# ProPrj_picoballoon-tracker_2025-08-19.net
KiCad netlist of a schematic drawn in EasyEDA Pro
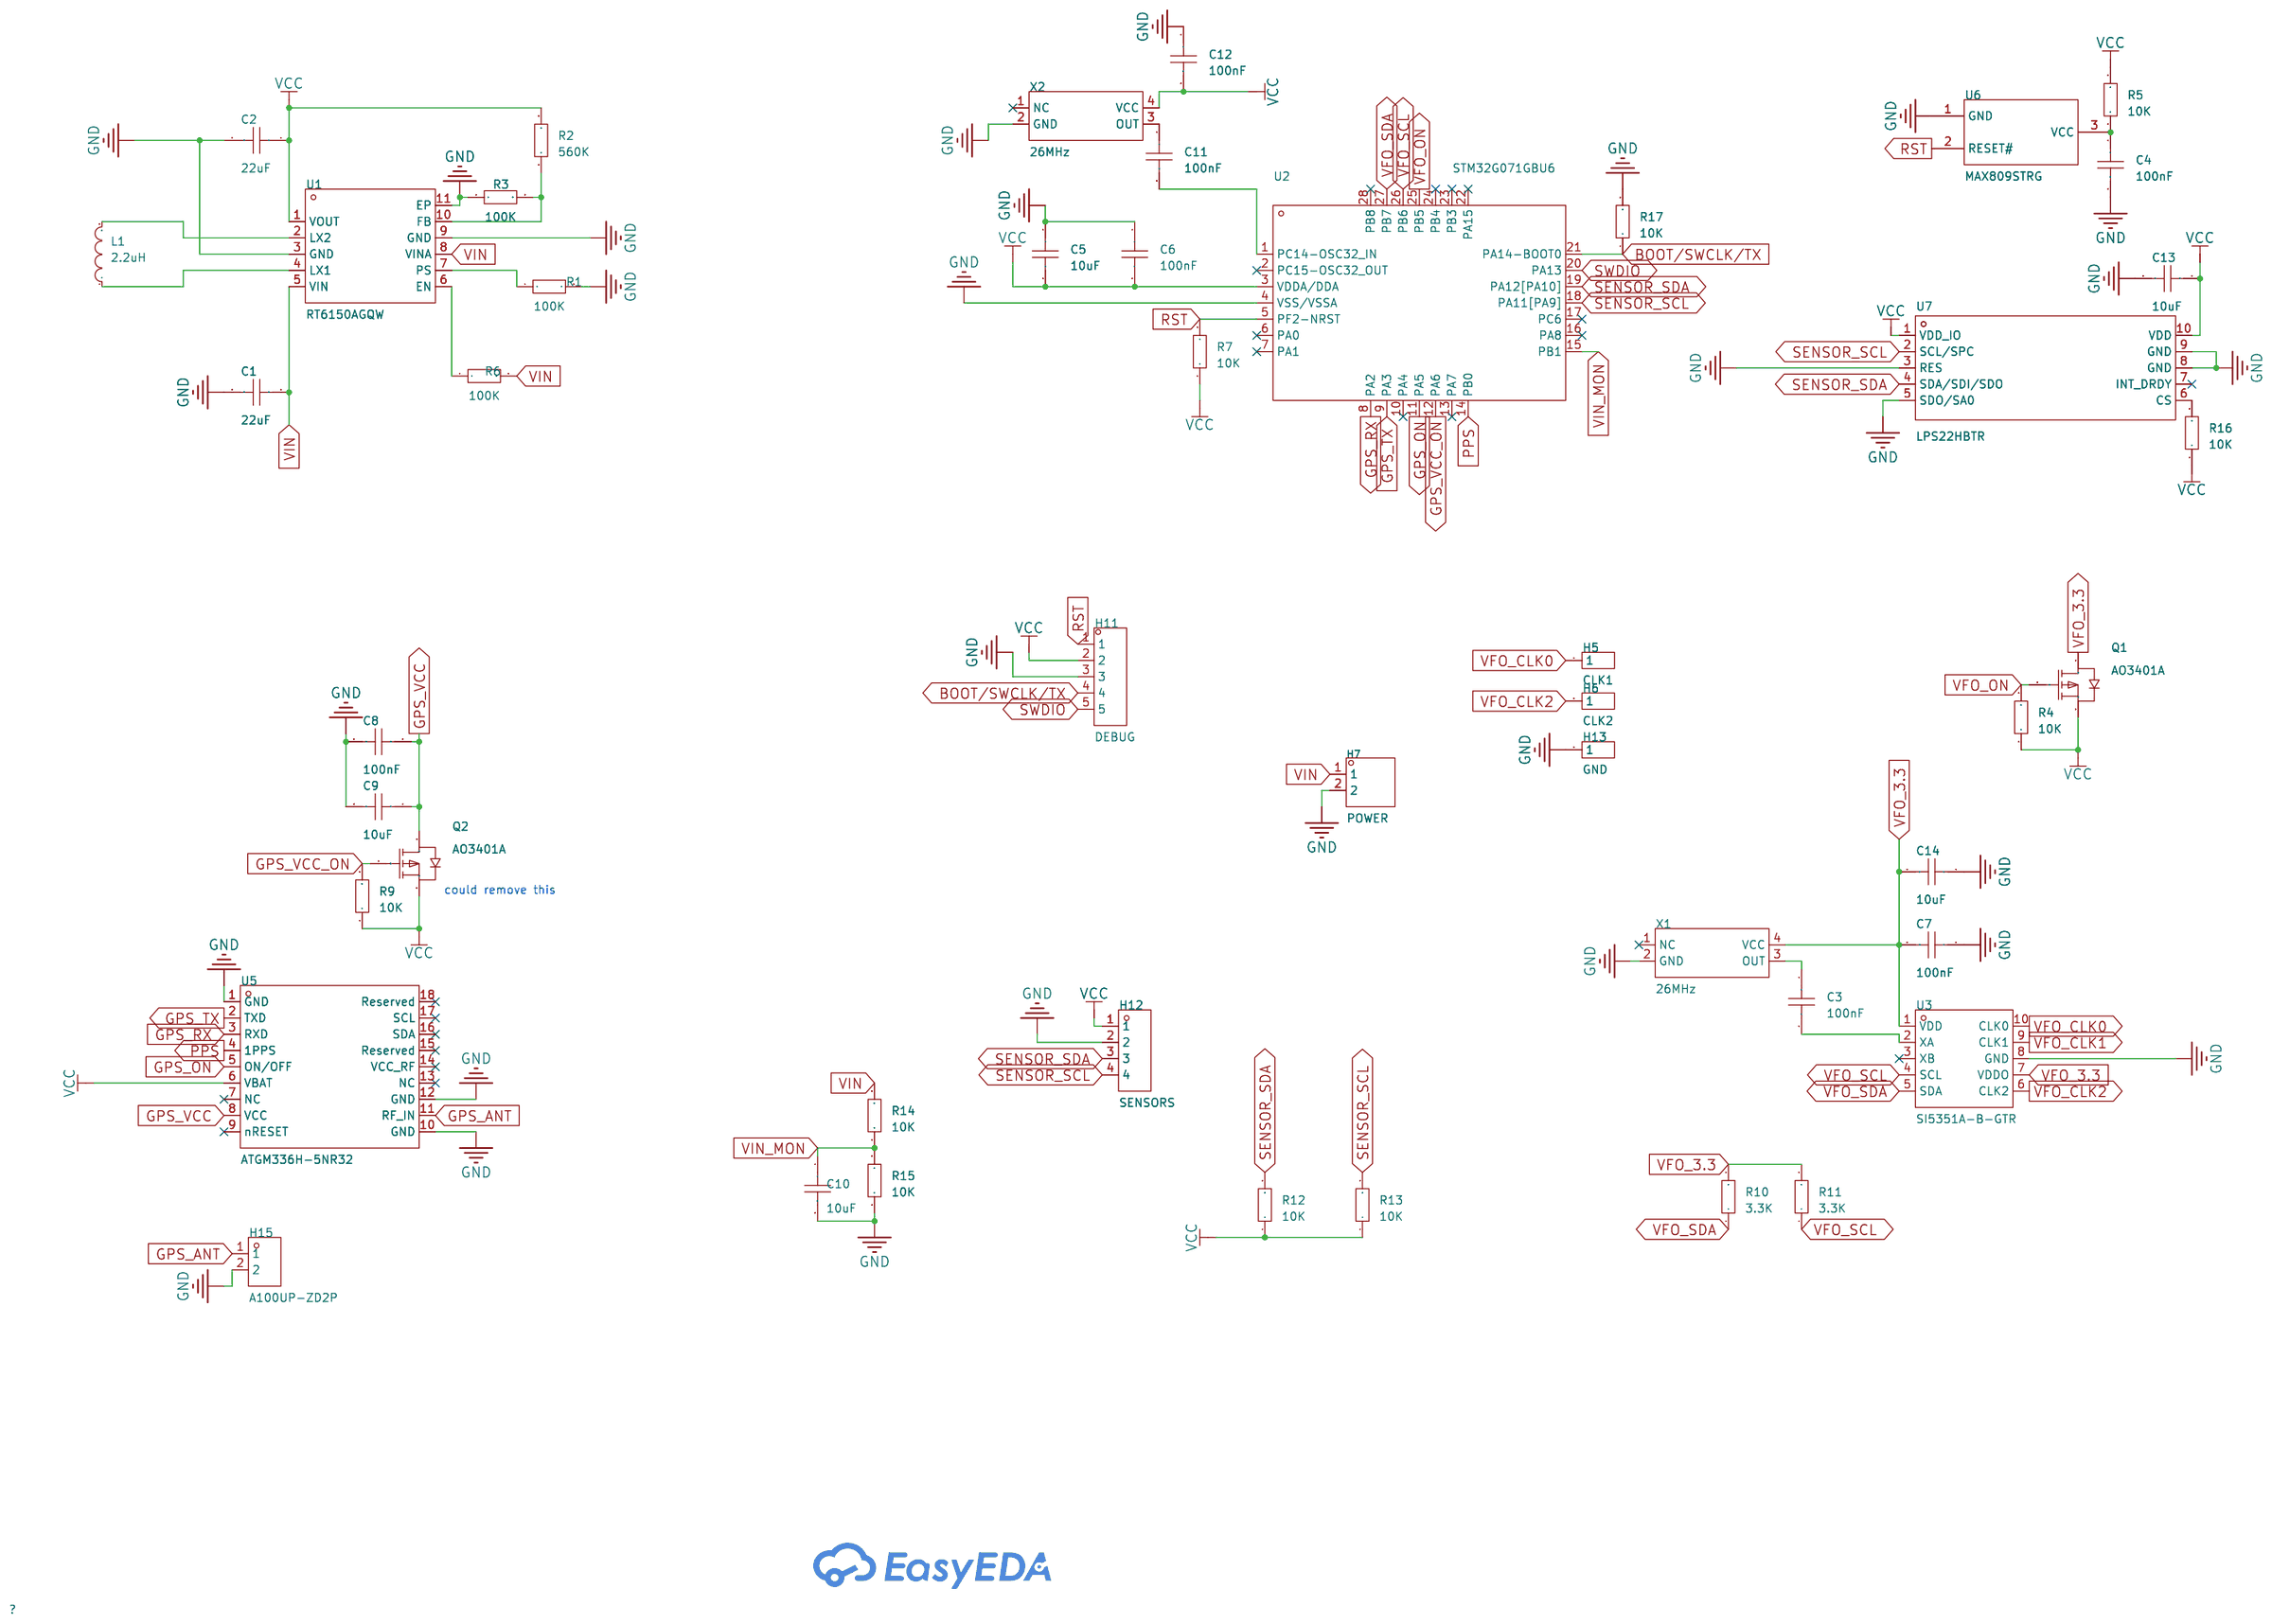
[diagram p0: schematic sheet]

(export (version "E")
  (design (tool "Eeschema 10.0.6"))
  (components
    (comp (ref "C1")
      (value "22uF")
      (footprint "easyedapro:C0402")
      (libsource (lib "easyedapro") (part "CAP"))
    )
    (comp (ref "C2")
      (value "22uF")
      (footprint "easyedapro:C0402")
      (libsource (lib "easyedapro") (part "CAP"))
    )
    (comp (ref "C3")
      (value "100nF")
      (footprint "easyedapro:C0402")
      (libsource (lib "easyedapro") (part "CAP"))
    )
    (comp (ref "C4")
      (value "100nF")
      (footprint "easyedapro:C0402")
      (libsource (lib "easyedapro") (part "CAP"))
    )
    (comp (ref "C5")
      (value "10uF")
      (footprint "easyedapro:C0402")
      (libsource (lib "easyedapro") (part "CAP"))
    )
    (comp (ref "C6")
      (value "100nF")
      (footprint "easyedapro:C0402")
      (libsource (lib "easyedapro") (part "CAP"))
    )
    (comp (ref "C7")
      (value "100nF")
      (footprint "easyedapro:C0402")
      (libsource (lib "easyedapro") (part "CAP"))
    )
    (comp (ref "C8")
      (value "100nF")
      (footprint "easyedapro:C0402")
      (libsource (lib "easyedapro") (part "CAP"))
    )
    (comp (ref "C9")
      (value "10uF")
      (footprint "easyedapro:C0402")
      (libsource (lib "easyedapro") (part "CAP"))
    )
    (comp (ref "C10")
      (value "10uF")
      (footprint "easyedapro:C0402")
      (libsource (lib "easyedapro") (part "CAP"))
    )
    (comp (ref "C11")
      (value "100nF")
      (footprint "easyedapro:C0402")
      (libsource (lib "easyedapro") (part "CAP"))
    )
    (comp (ref "C12")
      (value "100nF")
      (footprint "easyedapro:C0402")
      (libsource (lib "easyedapro") (part "CAP"))
    )
    (comp (ref "C13")
      (value "10uF")
      (footprint "easyedapro:C0402")
      (libsource (lib "easyedapro") (part "CAP"))
    )
    (comp (ref "C14")
      (value "10uF")
      (footprint "easyedapro:C0402")
      (libsource (lib "easyedapro") (part "CAP"))
    )
    (comp (ref "H5")
      (value "CLK1")
      (footprint "easyedapro:HDR-TH_1P-V-M_XKB_X4611WV-01I-C28D40")
      (libsource (lib "easyedapro") (part "HDR_1x1"))
    )
    (comp (ref "H6")
      (value "CLK2")
      (footprint "easyedapro:HDR-TH_1P-V-M_XKB_X4611WV-01I-C28D40")
      (libsource (lib "easyedapro") (part "HDR_1x1"))
    )
    (comp (ref "H7")
      (value "POWER")
      (footprint "easyedapro:HDR-TH_2P-P2.54-V-M-1")
      (libsource (lib "easyedapro") (part "210S-1*2P L=11.6MMGold-plated black"))
    )
    (comp (ref "H11")
      (value "DEBUG")
      (footprint "easyedapro:HDR-TH_5P-P2.54-V-M")
      (libsource (lib "easyedapro") (part "MTP125-1105S1"))
    )
    (comp (ref "H12")
      (value "SENSORS")
      (footprint "easyedapro:HDR-TH_ZX-PZ1.0-1-4PZZ")
      (fields
        (field (name "Manufacturer Part") "ZX-PZ1.0-1-4PZZ")
        (field (name "Manufacturer") "Megastar(兆星)")
      )
      (libsource (lib "easyedapro") (part "ZX-PZ1.0-1-4PZZ"))
    )
    (comp (ref "H13")
      (value "GND")
      (footprint "easyedapro:HDR-TH_1P-V-M_XKB_X4611WV-01I-C28D40")
      (libsource (lib "easyedapro") (part "HDR_1x1"))
    )
    (comp (ref "H15")
      (value "A100UP-ZD2P")
      (footprint "easyedapro:HDR-TH_2P-P1.00-V-M")
      (fields (field (name "Manufacturer") "BXCONN(宝讯)"))
      (libsource (lib "easyedapro") (part "A100UP-ZD2P"))
    )
    (comp (ref "L1")
      (value "2.2uH")
      (footprint "easyedapro:L0805")
      (libsource (lib "easyedapro") (part "电感"))
    )
    (comp (ref "Q1")
      (value "AO3401A")
      (footprint "easyedapro:SOT-23_L2.9-W1.3-P1.90-LS2.4-BR")
      (fields (field (name "Manufacturer") "AOS"))
      (libsource (lib "easyedapro") (part "AO3401A"))
    )
    (comp (ref "Q2")
      (value "AO3401A")
      (footprint "easyedapro:SOT-23_L2.9-W1.3-P1.90-LS2.4-BR")
      (fields (field (name "Manufacturer") "AOS"))
      (libsource (lib "easyedapro") (part "AO3401A"))
    )
    (comp (ref "R1")
      (value "100K")
      (footprint "easyedapro:R0402")
      (libsource (lib "easyedapro") (part "Res"))
    )
    (comp (ref "R2")
      (value "560K")
      (footprint "easyedapro:R0402")
      (libsource (lib "easyedapro") (part "Res"))
    )
    (comp (ref "R3")
      (value "100K")
      (footprint "easyedapro:R0402")
      (libsource (lib "easyedapro") (part "Res"))
    )
    (comp (ref "R4") (value "10K") (footprint "easyedapro:R0402") (libsource (lib "easyedapro") (part "Res")))
    (comp (ref "R5") (value "10K") (footprint "easyedapro:R0402") (libsource (lib "easyedapro") (part "Res")))
    (comp (ref "R6")
      (value "100K")
      (footprint "easyedapro:R0402")
      (libsource (lib "easyedapro") (part "Res"))
    )
    (comp (ref "R7") (value "10K") (footprint "easyedapro:R0402") (libsource (lib "easyedapro") (part "Res")))
    (comp (ref "R9") (value "10K") (footprint "easyedapro:R0402") (libsource (lib "easyedapro") (part "Res")))
    (comp (ref "R10")
      (value "3.3K")
      (footprint "easyedapro:R0402")
      (libsource (lib "easyedapro") (part "Res"))
    )
    (comp (ref "R11")
      (value "3.3K")
      (footprint "easyedapro:R0402")
      (libsource (lib "easyedapro") (part "Res"))
    )
    (comp (ref "R12")
      (value "10K")
      (footprint "easyedapro:R0402")
      (libsource (lib "easyedapro") (part "Res"))
    )
    (comp (ref "R13")
      (value "10K")
      (footprint "easyedapro:R0402")
      (libsource (lib "easyedapro") (part "Res"))
    )
    (comp (ref "R14")
      (value "10K")
      (footprint "easyedapro:R0402")
      (libsource (lib "easyedapro") (part "Res"))
    )
    (comp (ref "R15")
      (value "10K")
      (footprint "easyedapro:R0402")
      (libsource (lib "easyedapro") (part "Res"))
    )
    (comp (ref "R16")
      (value "10K")
      (footprint "easyedapro:R0402")
      (libsource (lib "easyedapro") (part "Res"))
    )
    (comp (ref "R17")
      (value "10K")
      (footprint "easyedapro:R0402")
      (libsource (lib "easyedapro") (part "Res"))
    )
    (comp (ref "U1")
      (value "RT6150AGQW")
      (footprint "easyedapro:WDFN-10_L3.0-W3.0-P0.50-BL-EP")
      (fields (field (name "Manufacturer") "RICHTEK(立锜)"))
      (libsource (lib "easyedapro") (part "RT6150AGQW"))
    )
    (comp (ref "U2")
      (value "STM32G071GBU6")
      (footprint "easyedapro:UFQFPN-28_L4.0-W4.0-P0.50-BL")
      (fields (field (name "Manufacturer") "ST(意法半导体)"))
      (libsource (lib "easyedapro") (part "STM32G071GBU6"))
    )
    (comp (ref "U3")
      (value "SI5351A-B-GTR")
      (footprint "easyedapro:MSOP-10_L3.0-W3.0-P0.50-LS5.0-BL")
      (fields (field (name "Manufacturer") "SKYWORKS/SILICON LABS(芯科)"))
      (libsource (lib "easyedapro") (part "SI5351A-B-GTR"))
    )
    (comp (ref "U5")
      (value "ATGM336H-5NR32")
      (footprint "easyedapro:GPS-SMD_18P-L10.1-W9.7-P1.10-TL")
      (fields (field (name "Manufacturer") "杭州中科微"))
      (libsource (lib "easyedapro") (part "ATGM336H-5NR-32"))
    )
    (comp (ref "U6")
      (value "MAX809STRG")
      (footprint "easyedapro:SOT-23-3_L2.9-W1.6-P1.90-LS2.8-BR")
      (fields (field (name "Manufacturer") "onsemi(安森美)"))
      (libsource (lib "easyedapro") (part "MAX809STRG"))
    )
    (comp (ref "U7")
      (value "LPS22HBTR")
      (footprint "easyedapro:HLGA-10L_LPS22HBTR")
      (fields (field (name "Manufacturer") "ST(意法半导体)"))
      (libsource (lib "easyedapro") (part "LPS22HBTR"))
    )
    (comp (ref "X1")
      (value "26MHz")
      (footprint "easyedapro:OSC-SMD_4P-L2.5-W2.0-BL_X1G0042110003")
      (fields (field (name "Manufacturer Part") "X1G0042110003") (field (name "Manufacturer") "EPSON(爱普生)"))
      (libsource (lib "easyedapro") (part "X1G0042110003_C3013793"))
    )
    (comp (ref "X2")
      (value "26MHz")
      (footprint "easyedapro:OSC-SMD_4P-L2.5-W2.0-BL_X1G0042110003")
      (fields (field (name "Manufacturer Part") "X1G0042110003") (field (name "Manufacturer") "EPSON(爱普生)"))
      (libsource (lib "easyedapro") (part "X1G0042110003_C3013793"))
    )
  )
  (nets
    (net (code "1") (name "BOOT{slash}SWCLK{slash}TX") (class "Default")
      (node (ref "H11") (pin "4") (pinfunction "4_4") (pintype "input"))
      (node (ref "R17") (pin "1") (pinfunction "1_1") (pintype "input"))
      (node (ref "U2") (pin "21") (pinfunction "PA14-BOOT0_21") (pintype "unspecified"))
    )
    (net (code "2") (name "GND") (class "Default")
      (node (ref "C1") (pin "2") (pinfunction "2_2") (pintype "input"))
      (node (ref "C10") (pin "2") (pinfunction "2_2") (pintype "input"))
      (node (ref "C12") (pin "1") (pinfunction "1_1") (pintype "input"))
      (node (ref "C13") (pin "2") (pinfunction "2_2") (pintype "input"))
      (node (ref "C14") (pin "1") (pinfunction "1_1") (pintype "input"))
      (node (ref "C2") (pin "2") (pinfunction "2_2") (pintype "input"))
      (node (ref "C4") (pin "2") (pinfunction "2_2") (pintype "input"))
      (node (ref "C5") (pin "1") (pinfunction "1_1") (pintype "input"))
      (node (ref "C6") (pin "1") (pinfunction "1_1") (pintype "input"))
      (node (ref "C7") (pin "1") (pinfunction "1_1") (pintype "input"))
      (node (ref "C8") (pin "2") (pinfunction "2_2") (pintype "input"))
      (node (ref "C9") (pin "2") (pinfunction "2_2") (pintype "input"))
      (node (ref "H11") (pin "3") (pinfunction "3_3") (pintype "input"))
      (node (ref "H12") (pin "2") (pinfunction "2_2") (pintype "unspecified"))
      (node (ref "H13") (pin "1") (pinfunction "1_1") (pintype "unspecified"))
      (node (ref "H15") (pin "2") (pinfunction "2_2") (pintype "unspecified"))
      (node (ref "H7") (pin "2") (pinfunction "2_2") (pintype "input"))
      (node (ref "R1") (pin "2") (pinfunction "2_2") (pintype "input"))
      (node (ref "R15") (pin "1") (pinfunction "1_1") (pintype "input"))
      (node (ref "R17") (pin "2") (pinfunction "2_2") (pintype "input"))
      (node (ref "R3") (pin "1") (pinfunction "1_1") (pintype "input"))
      (node (ref "U1") (pin "11") (pinfunction "EP_11") (pintype "unspecified"))
      (node (ref "U1") (pin "3") (pinfunction "GND_3") (pintype "unspecified"))
      (node (ref "U1") (pin "9") (pinfunction "GND_9") (pintype "unspecified"))
      (node (ref "U2") (pin "4") (pinfunction "VSS/VSSA_4") (pintype "unspecified"))
      (node (ref "U3") (pin "8") (pinfunction "GND_8") (pintype "unspecified"))
      (node (ref "U5") (pin "1") (pinfunction "GND_1") (pintype "unspecified"))
      (node (ref "U5") (pin "10") (pinfunction "GND_10") (pintype "unspecified"))
      (node (ref "U5") (pin "12") (pinfunction "GND_12") (pintype "unspecified"))
      (node (ref "U6") (pin "1") (pinfunction "GND_1") (pintype "unspecified"))
      (node (ref "U7") (pin "3") (pinfunction "RES_3") (pintype "unspecified"))
      (node (ref "U7") (pin "5") (pinfunction "SDO/SA0_5") (pintype "unspecified"))
      (node (ref "U7") (pin "8") (pinfunction "GND_8") (pintype "unspecified"))
      (node (ref "U7") (pin "9") (pinfunction "GND_9") (pintype "unspecified"))
      (node (ref "X1") (pin "2") (pinfunction "GND_2") (pintype "unspecified"))
      (node (ref "X2") (pin "2") (pinfunction "GND_2") (pintype "unspecified"))
    )
    (net (code "3") (name "GPS_ANT") (class "Default")
      (node (ref "H15") (pin "1") (pinfunction "1_1") (pintype "unspecified"))
      (node (ref "U5") (pin "11") (pinfunction "RF_IN_11") (pintype "unspecified"))
    )
    (net (code "4") (name "GPS_ON") (class "Default")
      (node (ref "U2") (pin "11") (pinfunction "PA5_11") (pintype "unspecified"))
      (node (ref "U5") (pin "5") (pinfunction "ON/OFF_5") (pintype "unspecified"))
    )
    (net (code "5") (name "GPS_RX") (class "Default")
      (node (ref "U2") (pin "8") (pinfunction "PA2_8") (pintype "unspecified"))
      (node (ref "U5") (pin "3") (pinfunction "RXD_3") (pintype "unspecified"))
    )
    (net (code "6") (name "GPS_TX") (class "Default")
      (node (ref "U2") (pin "9") (pinfunction "PA3_9") (pintype "unspecified"))
      (node (ref "U5") (pin "2") (pinfunction "TXD_2") (pintype "unspecified"))
    )
    (net (code "7") (name "GPS_VCC") (class "Default")
      (node (ref "C8") (pin "1") (pinfunction "1_1") (pintype "input"))
      (node (ref "C9") (pin "1") (pinfunction "1_1") (pintype "input"))
      (node (ref "Q2") (pin "3") (pinfunction "D_3") (pintype "unspecified"))
      (node (ref "U5") (pin "8") (pinfunction "VCC_8") (pintype "unspecified"))
    )
    (net (code "8") (name "GPS_VCC_ON") (class "Default")
      (node (ref "Q2") (pin "1") (pinfunction "G_1") (pintype "unspecified"))
      (node (ref "R9") (pin "2") (pinfunction "2_2") (pintype "input"))
      (node (ref "U2") (pin "12") (pinfunction "PA6_12") (pintype "unspecified"))
    )
    (net (code "9") (name "Net-(U1-EN)") (class "Default")
      (node (ref "R6") (pin "1") (pinfunction "1_1") (pintype "input"))
      (node (ref "U1") (pin "6") (pinfunction "EN_6") (pintype "unspecified"))
    )
    (net (code "10") (name "Net-(U1-FB)") (class "Default")
      (node (ref "R2") (pin "1") (pinfunction "1_1") (pintype "input"))
      (node (ref "R3") (pin "2") (pinfunction "2_2") (pintype "input"))
      (node (ref "U1") (pin "10") (pinfunction "FB_10") (pintype "unspecified"))
    )
    (net (code "11") (name "Net-(U1-LX1)") (class "Default")
      (node (ref "L1") (pin "1") (pinfunction "1_1") (pintype "input"))
      (node (ref "U1") (pin "4") (pinfunction "LX1_4") (pintype "unspecified"))
    )
    (net (code "12") (name "Net-(U1-LX2)") (class "Default")
      (node (ref "L1") (pin "2") (pinfunction "2_2") (pintype "input"))
      (node (ref "U1") (pin "2") (pinfunction "LX2_2") (pintype "unspecified"))
    )
    (net (code "13") (name "Net-(U1-PS)") (class "Default")
      (node (ref "R1") (pin "1") (pinfunction "1_1") (pintype "input"))
      (node (ref "U1") (pin "7") (pinfunction "PS_7") (pintype "unspecified"))
    )
    (net (code "14") (name "Net-(U2-PC14-OSC32_IN)") (class "Default")
      (node (ref "C11") (pin "2") (pinfunction "2_2") (pintype "input"))
      (node (ref "U2") (pin "1") (pinfunction "PC14-OSC32_IN_1") (pintype "unspecified"))
    )
    (net (code "15") (name "Net-(U3-XA)") (class "Default")
      (node (ref "C3") (pin "2") (pinfunction "2_2") (pintype "input"))
      (node (ref "U3") (pin "2") (pinfunction "XA_2") (pintype "unspecified"))
    )
    (net (code "16") (name "Net-(U6-VCC)") (class "Default")
      (node (ref "C4") (pin "1") (pinfunction "1_1") (pintype "input"))
      (node (ref "R5") (pin "1") (pinfunction "1_1") (pintype "input"))
      (node (ref "U6") (pin "3") (pinfunction "VCC_3") (pintype "unspecified"))
    )
    (net (code "17") (name "Net-(U7-CS)") (class "Default")
      (node (ref "R16") (pin "2") (pinfunction "2_2") (pintype "input"))
      (node (ref "U7") (pin "6") (pinfunction "CS_6") (pintype "unspecified"))
    )
    (net (code "18") (name "Net-(X1-OUT)") (class "Default")
      (node (ref "C3") (pin "1") (pinfunction "1_1") (pintype "input"))
      (node (ref "X1") (pin "3") (pinfunction "OUT_3") (pintype "unspecified"))
    )
    (net (code "19") (name "Net-(X2-OUT)") (class "Default")
      (node (ref "C11") (pin "1") (pinfunction "1_1") (pintype "input"))
      (node (ref "X2") (pin "3") (pinfunction "OUT_3") (pintype "unspecified"))
    )
    (net (code "20") (name "PPS") (class "Default")
      (node (ref "U2") (pin "14") (pinfunction "PB0_14") (pintype "unspecified"))
      (node (ref "U5") (pin "4") (pinfunction "1PPS_4") (pintype "unspecified"))
    )
    (net (code "21") (name "RST") (class "Default")
      (node (ref "H11") (pin "1") (pinfunction "1_1") (pintype "input"))
      (node (ref "R7") (pin "2") (pinfunction "2_2") (pintype "input"))
      (node (ref "U2") (pin "5") (pinfunction "PF2-NRST_5") (pintype "unspecified"))
      (node (ref "U6") (pin "2") (pinfunction "RESET#_2") (pintype "unspecified"))
    )
    (net (code "22") (name "SENSOR_SCL") (class "Default")
      (node (ref "H12") (pin "4") (pinfunction "4_4") (pintype "unspecified"))
      (node (ref "R13") (pin "2") (pinfunction "2_2") (pintype "input"))
      (node (ref "U2") (pin "18") (pinfunction "PA11[PA9]_18") (pintype "unspecified"))
      (node (ref "U7") (pin "2") (pinfunction "SCL/SPC_2") (pintype "unspecified"))
    )
    (net (code "23") (name "SENSOR_SDA") (class "Default")
      (node (ref "H12") (pin "3") (pinfunction "3_3") (pintype "unspecified"))
      (node (ref "R12") (pin "2") (pinfunction "2_2") (pintype "input"))
      (node (ref "U2") (pin "19") (pinfunction "PA12[PA10]_19") (pintype "unspecified"))
      (node (ref "U7") (pin "4") (pinfunction "SDA/SDI/SDO_4") (pintype "unspecified"))
    )
    (net (code "24") (name "SWDIO") (class "Default")
      (node (ref "H11") (pin "5") (pinfunction "5_5") (pintype "input"))
      (node (ref "U2") (pin "20") (pinfunction "PA13_20") (pintype "unspecified"))
    )
    (net (code "25") (name "VCC") (class "Default")
      (node (ref "C12") (pin "2") (pinfunction "2_2") (pintype "input"))
      (node (ref "C13") (pin "1") (pinfunction "1_1") (pintype "input"))
      (node (ref "C2") (pin "1") (pinfunction "1_1") (pintype "input"))
      (node (ref "C5") (pin "2") (pinfunction "2_2") (pintype "input"))
      (node (ref "C6") (pin "2") (pinfunction "2_2") (pintype "input"))
      (node (ref "H11") (pin "2") (pinfunction "2_2") (pintype "input"))
      (node (ref "H12") (pin "1") (pinfunction "1_1") (pintype "unspecified"))
      (node (ref "Q1") (pin "2") (pinfunction "S_2") (pintype "unspecified"))
      (node (ref "Q2") (pin "2") (pinfunction "S_2") (pintype "unspecified"))
      (node (ref "R12") (pin "1") (pinfunction "1_1") (pintype "input"))
      (node (ref "R13") (pin "1") (pinfunction "1_1") (pintype "input"))
      (node (ref "R16") (pin "1") (pinfunction "1_1") (pintype "input"))
      (node (ref "R2") (pin "2") (pinfunction "2_2") (pintype "input"))
      (node (ref "R4") (pin "1") (pinfunction "1_1") (pintype "input"))
      (node (ref "R5") (pin "2") (pinfunction "2_2") (pintype "input"))
      (node (ref "R7") (pin "1") (pinfunction "1_1") (pintype "input"))
      (node (ref "R9") (pin "1") (pinfunction "1_1") (pintype "input"))
      (node (ref "U1") (pin "1") (pinfunction "VOUT_1") (pintype "unspecified"))
      (node (ref "U2") (pin "3") (pinfunction "VDDA/DDA_3") (pintype "unspecified"))
      (node (ref "U5") (pin "6") (pinfunction "VBAT_6") (pintype "unspecified"))
      (node (ref "U7") (pin "1") (pinfunction "VDD_IO_1") (pintype "unspecified"))
      (node (ref "U7") (pin "10") (pinfunction "VDD_10") (pintype "unspecified"))
      (node (ref "X2") (pin "4") (pinfunction "VCC_4") (pintype "unspecified"))
    )
    (net (code "26") (name "VFO_3.3") (class "Default")
      (node (ref "C14") (pin "2") (pinfunction "2_2") (pintype "input"))
      (node (ref "C7") (pin "2") (pinfunction "2_2") (pintype "input"))
      (node (ref "Q1") (pin "3") (pinfunction "D_3") (pintype "unspecified"))
      (node (ref "R10") (pin "2") (pinfunction "2_2") (pintype "input"))
      (node (ref "R11") (pin "2") (pinfunction "2_2") (pintype "input"))
      (node (ref "U3") (pin "1") (pinfunction "VDD_1") (pintype "unspecified"))
      (node (ref "U3") (pin "7") (pinfunction "VDDO_7") (pintype "unspecified"))
      (node (ref "X1") (pin "4") (pinfunction "VCC_4") (pintype "unspecified"))
    )
    (net (code "27") (name "VFO_CLK0") (class "Default")
      (node (ref "H5") (pin "1") (pinfunction "1_1") (pintype "unspecified"))
      (node (ref "U3") (pin "10") (pinfunction "CLK0_10") (pintype "unspecified"))
    )
    (net (code "28") (name "VFO_CLK1") (class "Default")
      (node (ref "U3") (pin "9") (pinfunction "CLK1_9") (pintype "unspecified"))
    )
    (net (code "29") (name "VFO_CLK2") (class "Default")
      (node (ref "H6") (pin "1") (pinfunction "1_1") (pintype "unspecified"))
      (node (ref "U3") (pin "6") (pinfunction "CLK2_6") (pintype "unspecified"))
    )
    (net (code "30") (name "VFO_ON") (class "Default")
      (node (ref "Q1") (pin "1") (pinfunction "G_1") (pintype "unspecified"))
      (node (ref "R4") (pin "2") (pinfunction "2_2") (pintype "input"))
      (node (ref "U2") (pin "25") (pinfunction "PB5_25") (pintype "unspecified"))
    )
    (net (code "31") (name "VFO_SCL") (class "Default")
      (node (ref "R11") (pin "1") (pinfunction "1_1") (pintype "input"))
      (node (ref "U2") (pin "26") (pinfunction "PB6_26") (pintype "unspecified"))
      (node (ref "U3") (pin "4") (pinfunction "SCL_4") (pintype "unspecified"))
    )
    (net (code "32") (name "VFO_SDA") (class "Default")
      (node (ref "R10") (pin "1") (pinfunction "1_1") (pintype "input"))
      (node (ref "U2") (pin "27") (pinfunction "PB7_27") (pintype "unspecified"))
      (node (ref "U3") (pin "5") (pinfunction "SDA_5") (pintype "unspecified"))
    )
    (net (code "33") (name "VIN") (class "Default")
      (node (ref "C1") (pin "1") (pinfunction "1_1") (pintype "input"))
      (node (ref "H7") (pin "1") (pinfunction "1_1") (pintype "input"))
      (node (ref "R14") (pin "2") (pinfunction "2_2") (pintype "input"))
      (node (ref "R6") (pin "2") (pinfunction "2_2") (pintype "input"))
      (node (ref "U1") (pin "5") (pinfunction "VIN_5") (pintype "unspecified"))
      (node (ref "U1") (pin "8") (pinfunction "VINA_8") (pintype "unspecified"))
    )
    (net (code "34") (name "VIN_MON") (class "Default")
      (node (ref "C10") (pin "1") (pinfunction "1_1") (pintype "input"))
      (node (ref "R14") (pin "1") (pinfunction "1_1") (pintype "input"))
      (node (ref "R15") (pin "2") (pinfunction "2_2") (pintype "input"))
      (node (ref "U2") (pin "15") (pinfunction "PB1_15") (pintype "unspecified"))
    )
    (net (code "35") (name "unconnected-(U2-PA0-Pad6)") (class "Default")
      (node (ref "U2") (pin "6") (pinfunction "PA0_6") (pintype "unspecified+no_connect"))
    )
    (net (code "36") (name "unconnected-(U2-PA1-Pad7)") (class "Default")
      (node (ref "U2") (pin "7") (pinfunction "PA1_7") (pintype "unspecified+no_connect"))
    )
    (net (code "37") (name "unconnected-(U2-PA4-Pad10)") (class "Default")
      (node (ref "U2") (pin "10") (pinfunction "PA4_10") (pintype "unspecified+no_connect"))
    )
    (net (code "38") (name "unconnected-(U2-PA7-Pad13)") (class "Default")
      (node (ref "U2") (pin "13") (pinfunction "PA7_13") (pintype "unspecified+no_connect"))
    )
    (net (code "39") (name "unconnected-(U2-PA8-Pad16)") (class "Default")
      (node (ref "U2") (pin "16") (pinfunction "PA8_16") (pintype "unspecified+no_connect"))
    )
    (net (code "40") (name "unconnected-(U2-PA15-Pad22)") (class "Default")
      (node (ref "U2") (pin "22") (pinfunction "PA15_22") (pintype "unspecified+no_connect"))
    )
    (net (code "41") (name "unconnected-(U2-PB3-Pad23)") (class "Default")
      (node (ref "U2") (pin "23") (pinfunction "PB3_23") (pintype "unspecified+no_connect"))
    )
    (net (code "42") (name "unconnected-(U2-PB4-Pad24)") (class "Default")
      (node (ref "U2") (pin "24") (pinfunction "PB4_24") (pintype "unspecified+no_connect"))
    )
    (net (code "43") (name "unconnected-(U2-PB8-Pad28)") (class "Default")
      (node (ref "U2") (pin "28") (pinfunction "PB8_28") (pintype "unspecified+no_connect"))
    )
    (net (code "44") (name "unconnected-(U2-PC6-Pad17)") (class "Default")
      (node (ref "U2") (pin "17") (pinfunction "PC6_17") (pintype "unspecified+no_connect"))
    )
    (net (code "45") (name "unconnected-(U2-PC15-OSC32_OUT-Pad2)") (class "Default")
      (node (ref "U2") (pin "2") (pinfunction "PC15-OSC32_OUT_2") (pintype "unspecified+no_connect"))
    )
    (net (code "46") (name "unconnected-(U3-XB-Pad3)") (class "Default")
      (node (ref "U3") (pin "3") (pinfunction "XB_3") (pintype "unspecified+no_connect"))
    )
    (net (code "47") (name "unconnected-(U5-NC-Pad7)") (class "Default")
      (node (ref "U5") (pin "7") (pinfunction "NC_7") (pintype "unspecified+no_connect"))
    )
    (net (code "48") (name "unconnected-(U5-NC-Pad13)") (class "Default")
      (node (ref "U5") (pin "13") (pinfunction "NC_13") (pintype "unspecified+no_connect"))
    )
    (net (code "49") (name "unconnected-(U5-Reserved-Pad15)") (class "Default")
      (node (ref "U5") (pin "15") (pinfunction "Reserved_15") (pintype "unspecified+no_connect"))
    )
    (net (code "50") (name "unconnected-(U5-Reserved-Pad18)") (class "Default")
      (node (ref "U5") (pin "18") (pinfunction "Reserved_18") (pintype "unspecified+no_connect"))
    )
    (net (code "51") (name "unconnected-(U5-SCL-Pad17)") (class "Default")
      (node (ref "U5") (pin "17") (pinfunction "SCL_17") (pintype "unspecified+no_connect"))
    )
    (net (code "52") (name "unconnected-(U5-SDA-Pad16)") (class "Default")
      (node (ref "U5") (pin "16") (pinfunction "SDA_16") (pintype "unspecified+no_connect"))
    )
    (net (code "53") (name "unconnected-(U5-VCC_RF-Pad14)") (class "Default")
      (node (ref "U5") (pin "14") (pinfunction "VCC_RF_14") (pintype "unspecified+no_connect"))
    )
    (net (code "54") (name "unconnected-(U5-nRESET-Pad9)") (class "Default")
      (node (ref "U5") (pin "9") (pinfunction "nRESET_9") (pintype "unspecified+no_connect"))
    )
    (net (code "55") (name "unconnected-(U7-INT_DRDY-Pad7)") (class "Default")
      (node (ref "U7") (pin "7") (pinfunction "INT_DRDY_7") (pintype "unspecified+no_connect"))
    )
    (net (code "56") (name "unconnected-(X1-NC-Pad1)") (class "Default")
      (node (ref "X1") (pin "1") (pinfunction "NC_1") (pintype "unspecified+no_connect"))
    )
    (net (code "57") (name "unconnected-(X2-NC-Pad1)") (class "Default")
      (node (ref "X2") (pin "1") (pinfunction "NC_1") (pintype "unspecified+no_connect"))
    )
  )
)
